# EInkHeader.net
KiCad netlist of a schematic drawn in Altium Designer
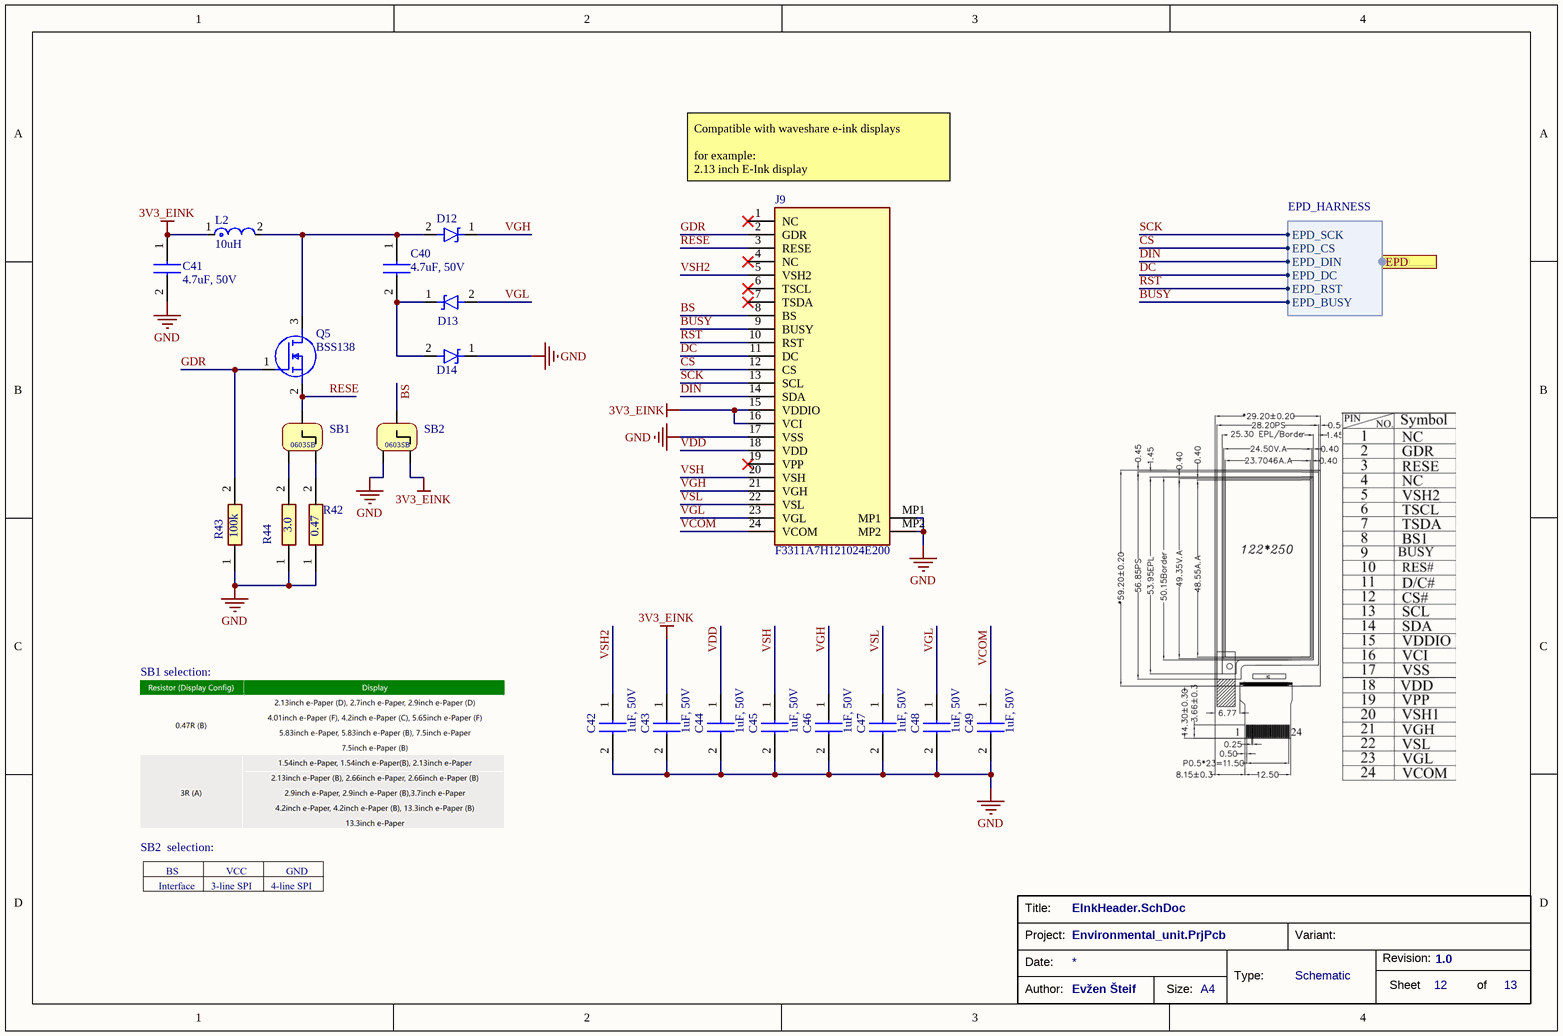
[diagram p0: EInkHeader.SchDoc]

(export (version "E")
  (design (tool "Eeschema 10.0.6"))
  (components
    (comp (ref "C40")
      (value "4.7uF, 50V")
      (footprint "SamacSys:CAPC2012X145N")
      (description "Capacitor")
      (fields
        (field (name "MANUFACTURER_PART_NUMBER") "GRM21BR61H475KE51L")
        (field (name "MOUSER PART NUMBER") "81-GRM21BR61H475KE1L")
      )
      (libsource (lib "*") (part "GRM21BR61H475KE51L"))
    )
    (comp (ref "C41")
      (value "4.7uF, 50V")
      (footprint "SamacSys:CAPC2012X145N")
      (description "Capacitor")
      (fields
        (field (name "MANUFACTURER_PART_NUMBER") "GRM21BR61H475KE51L")
        (field (name "MOUSER PART NUMBER") "81-GRM21BR61H475KE1L")
      )
      (libsource (lib "*") (part "GRM21BR61H475KE51L"))
    )
    (comp (ref "C42")
      (value "1uF, 50V")
      (footprint "SamacSys:CAPC1608X90N")
      (description "Capacitor")
      (fields
        (field (name "MANUFACTURER_PART_NUMBER") "GRT188R61H105KE13D")
        (field (name "MOUSER PART NUMBER") "81-GRT188R61H105KE3D")
      )
      (libsource (lib "*") (part "GRT188R61H105KE13D"))
    )
    (comp (ref "C43")
      (value "1uF, 50V")
      (footprint "SamacSys:CAPC1608X90N")
      (description "Capacitor")
      (fields
        (field (name "MANUFACTURER_PART_NUMBER") "GRT188R61H105KE13D")
        (field (name "MOUSER PART NUMBER") "81-GRT188R61H105KE3D")
      )
      (libsource (lib "*") (part "GRT188R61H105KE13D"))
    )
    (comp (ref "C44")
      (value "1uF, 50V")
      (footprint "SamacSys:CAPC1608X90N")
      (description "Capacitor")
      (fields
        (field (name "MANUFACTURER_PART_NUMBER") "GRT188R61H105KE13D")
        (field (name "MOUSER PART NUMBER") "81-GRT188R61H105KE3D")
      )
      (libsource (lib "*") (part "GRT188R61H105KE13D"))
    )
    (comp (ref "C45")
      (value "1uF, 50V")
      (footprint "SamacSys:CAPC1608X90N")
      (description "Capacitor")
      (fields
        (field (name "MANUFACTURER_PART_NUMBER") "GRT188R61H105KE13D")
        (field (name "MOUSER PART NUMBER") "81-GRT188R61H105KE3D")
      )
      (libsource (lib "*") (part "GRT188R61H105KE13D"))
    )
    (comp (ref "C46")
      (value "1uF, 50V")
      (footprint "SamacSys:CAPC1608X90N")
      (description "Capacitor")
      (fields
        (field (name "MANUFACTURER_PART_NUMBER") "GRT188R61H105KE13D")
        (field (name "MOUSER PART NUMBER") "81-GRT188R61H105KE3D")
      )
      (libsource (lib "*") (part "GRT188R61H105KE13D"))
    )
    (comp (ref "C47")
      (value "1uF, 50V")
      (footprint "SamacSys:CAPC1608X90N")
      (description "Capacitor")
      (fields
        (field (name "MANUFACTURER_PART_NUMBER") "GRT188R61H105KE13D")
        (field (name "MOUSER PART NUMBER") "81-GRT188R61H105KE3D")
      )
      (libsource (lib "*") (part "GRT188R61H105KE13D"))
    )
    (comp (ref "C48")
      (value "1uF, 50V")
      (footprint "SamacSys:CAPC1608X90N")
      (description "Capacitor")
      (fields
        (field (name "MANUFACTURER_PART_NUMBER") "GRT188R61H105KE13D")
        (field (name "MOUSER PART NUMBER") "81-GRT188R61H105KE3D")
      )
      (libsource (lib "*") (part "GRT188R61H105KE13D"))
    )
    (comp (ref "C49")
      (value "1uF, 50V")
      (footprint "SamacSys:CAPC1608X90N")
      (description "Capacitor")
      (fields
        (field (name "MANUFACTURER_PART_NUMBER") "GRT188R61H105KE13D")
        (field (name "MOUSER PART NUMBER") "81-GRT188R61H105KE3D")
      )
      (libsource (lib "*") (part "GRT188R61H105KE13D"))
    )
    (comp (ref "D12")
      (value "MBR0530T1G")
      (footprint "SamacSys:SOD3716X135N")
      (description "Diode")
      (fields (field (name "MOUSER PART NUMBER") "863-MBR0530T1G"))
      (libsource (lib "SamacSys") (part "MBR0530T1G"))
    )
    (comp (ref "D13")
      (value "MBR0530T1G")
      (footprint "SamacSys:SOD3716X135N")
      (description "Diode")
      (fields (field (name "MOUSER PART NUMBER") "863-MBR0530T1G"))
      (libsource (lib "SamacSys") (part "MBR0530T1G"))
    )
    (comp (ref "D14")
      (value "MBR0530T1G")
      (footprint "SamacSys:SOD3716X135N")
      (description "Diode")
      (fields (field (name "MOUSER PART NUMBER") "863-MBR0530T1G"))
      (libsource (lib "SamacSys") (part "MBR0530T1G"))
    )
    (comp (ref "J9")
      (value "F3311A7H121024E200")
      (footprint "SamacSys:F3311A7H121024E200")
      (description "Connector")
      (fields (field (name "MOUSER PART NUMBER") "649-311A7H121024E200"))
      (libsource (lib "SamacSys") (part "F3311A7H121024E200"))
    )
    (comp (ref "L2")
      (value "10uH")
      (footprint "FP-EPL2010_H1_05-MFG")
      (description "EPL2010-103MLC Power inductor, shielded, 20% tol, SMT, RoHS")
      (fields (field (name "TOLERANCE") "20%"))
      (libsource (lib "Altium Content Vault") (part "4cc4b267dca4c8e51f7102f422741d8"))
    )
    (comp (ref "Q5")
      (value "BSS138")
      (footprint "SamacSys:SOT95P240X120-3N")
      (description "MOSFET (N-Channel)")
      (fields (field (name "MOUSER PART NUMBER") "512-BSS138"))
      (libsource (lib "*") (part "BSS138"))
    )
    (comp (ref "R42")
      (value "0.47")
      (footprint "SamacSys:ERJ3_B_BQ_BW_LW_(0603)")
      (description "Resistor")
      (fields
        (field (name "MANUFACTURER_PART_NUMBER") "ERJ-3BQFR47V")
        (field (name "MOUSER PART NUMBER") "667-ERJ-3BQFR47V")
      )
      (libsource (lib "*") (part "ERJ-3BQFR47V"))
    )
    (comp (ref "R43")
      (value "100k")
      (footprint "SamacSys:RESC1005X35N")
      (description "Resistor")
      (fields
        (field (name "MANUFACTURER_PART_NUMBER") "RT0402FRE07100KL")
        (field (name "MOUSER PART NUMBER") "603-RT0402FRE07100KL")
      )
      (libsource (lib "*") (part "RT0402FRE07100KL"))
    )
    (comp (ref "R44")
      (value "3.0")
      (footprint "SamacSys:ERJ3_B_BQ_BW_LW_(0603)")
      (description "Resistor")
      (fields
        (field (name "MANUFACTURER_PART_NUMBER") "ERJ-3RQF3R0V")
        (field (name "MOUSER PART NUMBER") "667-ERJ-3RQF3R0V")
      )
      (libsource (lib "*") (part "ERJ-3RQF3R0V"))
    )
    (comp (ref "SB1")
      (value "SP0603_RIGHT")
      (footprint "SamacSys:SP0603-RIGHT")
      (libsource (lib "SamacSys") (part "SP0603_RIGHT"))
    )
    (comp (ref "SB2")
      (value "SP0603_RIGHT")
      (footprint "SamacSys:SP0603-RIGHT")
      (libsource (lib "SamacSys") (part "SP0603_RIGHT"))
    )
  )
  (nets
    (net (code "2") (name "/BS") (class "Default")
      (node (ref "J9") (pin "8") (pinfunction "BS_8") (pintype "passive"))
      (node (ref "SB2") (pin "1") (pinfunction "1_1") (pintype "passive"))
    )
    (net (code "3") (name "/BUSY") (class "Default")
      (node (ref "J9") (pin "9") (pinfunction "BUSY_9") (pintype "passive"))
    )
    (net (code "4") (name "/CS") (class "Default")
      (node (ref "J9") (pin "12") (pinfunction "CS_12") (pintype "passive"))
    )
    (net (code "5") (name "/DC") (class "Default")
      (node (ref "J9") (pin "11") (pinfunction "DC_11") (pintype "passive"))
    )
    (net (code "6") (name "/DIN") (class "Default")
      (node (ref "J9") (pin "14") (pinfunction "SDA_14") (pintype "passive"))
    )
    (net (code "7") (name "/GDR") (class "Default")
      (node (ref "J9") (pin "2") (pinfunction "GDR_2") (pintype "passive"))
      (node (ref "Q5") (pin "1") (pinfunction "G_1") (pintype "passive"))
      (node (ref "R43") (pin "2") (pinfunction "2_2") (pintype "passive"))
    )
    (net (code "8") (name "/RESE") (class "Default")
      (node (ref "J9") (pin "3") (pinfunction "RESE_3") (pintype "passive"))
      (node (ref "Q5") (pin "2") (pinfunction "S_2") (pintype "passive"))
      (node (ref "SB1") (pin "1") (pinfunction "1_1") (pintype "passive"))
    )
    (net (code "9") (name "/RST") (class "Default")
      (node (ref "J9") (pin "10") (pinfunction "RST_10") (pintype "passive"))
    )
    (net (code "10") (name "/SCK") (class "Default")
      (node (ref "J9") (pin "13") (pinfunction "SCL_13") (pintype "passive"))
    )
    (net (code "11") (name "/VCOM") (class "Default")
      (node (ref "C49") (pin "1") (pinfunction "1_1") (pintype "passive"))
      (node (ref "J9") (pin "24") (pinfunction "VCOM_24") (pintype "passive"))
    )
    (net (code "12") (name "/VDD") (class "Default")
      (node (ref "C44") (pin "1") (pinfunction "1_1") (pintype "passive"))
      (node (ref "J9") (pin "18") (pinfunction "VDD_18") (pintype "passive"))
    )
    (net (code "13") (name "/VGH") (class "Default")
      (node (ref "C46") (pin "1") (pinfunction "1_1") (pintype "passive"))
      (node (ref "D12") (pin "1") (pinfunction "K_1") (pintype "passive"))
      (node (ref "J9") (pin "21") (pinfunction "VGH_21") (pintype "passive"))
    )
    (net (code "14") (name "/VGL") (class "Default")
      (node (ref "C48") (pin "1") (pinfunction "1_1") (pintype "passive"))
      (node (ref "D13") (pin "2") (pinfunction "A_2") (pintype "passive"))
      (node (ref "J9") (pin "23") (pinfunction "VGL_23") (pintype "passive"))
    )
    (net (code "15") (name "/VSH") (class "Default")
      (node (ref "C45") (pin "1") (pinfunction "1_1") (pintype "passive"))
      (node (ref "J9") (pin "20") (pinfunction "VSH_20") (pintype "passive"))
    )
    (net (code "16") (name "/VSH2") (class "Default")
      (node (ref "C42") (pin "1") (pinfunction "1_1") (pintype "passive"))
      (node (ref "J9") (pin "5") (pinfunction "VSH2_5") (pintype "passive"))
    )
    (net (code "17") (name "/VSL") (class "Default")
      (node (ref "C47") (pin "1") (pinfunction "1_1") (pintype "passive"))
      (node (ref "J9") (pin "22") (pinfunction "VSL_22") (pintype "passive"))
    )
    (net (code "19") (name "3V3_EINK") (class "Default")
      (node (ref "C41") (pin "1") (pinfunction "1_1") (pintype "passive"))
      (node (ref "C43") (pin "1") (pinfunction "1_1") (pintype "passive"))
      (node (ref "J9") (pin "15") (pinfunction "VDDIO_15") (pintype "passive"))
      (node (ref "J9") (pin "16") (pinfunction "VCI_16") (pintype "passive"))
      (node (ref "L2") (pin "1") (pinfunction "1_1") (pintype "passive"))
      (node (ref "SB2") (pin "2") (pinfunction "2_2") (pintype "passive"))
    )
    (net (code "20") (name "GND") (class "Default")
      (node (ref "C41") (pin "2") (pinfunction "2_2") (pintype "passive"))
      (node (ref "C42") (pin "2") (pinfunction "2_2") (pintype "passive"))
      (node (ref "C43") (pin "2") (pinfunction "2_2") (pintype "passive"))
      (node (ref "C44") (pin "2") (pinfunction "2_2") (pintype "passive"))
      (node (ref "C45") (pin "2") (pinfunction "2_2") (pintype "passive"))
      (node (ref "C46") (pin "2") (pinfunction "2_2") (pintype "passive"))
      (node (ref "C47") (pin "2") (pinfunction "2_2") (pintype "passive"))
      (node (ref "C48") (pin "2") (pinfunction "2_2") (pintype "passive"))
      (node (ref "C49") (pin "2") (pinfunction "2_2") (pintype "passive"))
      (node (ref "D14") (pin "1") (pinfunction "K_1") (pintype "passive"))
      (node (ref "J9") (pin "17") (pinfunction "VSS_17") (pintype "passive"))
      (node (ref "J9") (pin "MP1") (pinfunction "MP1_MP1") (pintype "passive"))
      (node (ref "J9") (pin "MP2") (pinfunction "MP2_MP2") (pintype "passive"))
      (node (ref "R42") (pin "1") (pinfunction "1_1") (pintype "passive"))
      (node (ref "R43") (pin "1") (pinfunction "1_1") (pintype "passive"))
      (node (ref "R44") (pin "1") (pinfunction "1_1") (pintype "passive"))
      (node (ref "SB2") (pin "3") (pinfunction "3_3") (pintype "passive"))
    )
    (net (code "21") (name "Net-(D12-A)") (class "Default")
      (node (ref "C40") (pin "1") (pinfunction "1_1") (pintype "passive"))
      (node (ref "D12") (pin "2") (pinfunction "A_2") (pintype "passive"))
      (node (ref "L2") (pin "2") (pinfunction "2_2") (pintype "passive"))
      (node (ref "Q5") (pin "3") (pinfunction "D_3") (pintype "passive"))
    )
    (net (code "22") (name "Net-(D13-K)") (class "Default")
      (node (ref "C40") (pin "2") (pinfunction "2_2") (pintype "passive"))
      (node (ref "D13") (pin "1") (pinfunction "K_1") (pintype "passive"))
      (node (ref "D14") (pin "2") (pinfunction "A_2") (pintype "passive"))
    )
    (net (code "23") (name "Net-(R42-Pad2)") (class "Default")
      (node (ref "R42") (pin "2") (pinfunction "2_2") (pintype "passive"))
      (node (ref "SB1") (pin "2") (pinfunction "2_2") (pintype "passive"))
    )
    (net (code "24") (name "Net-(R44-Pad2)") (class "Default")
      (node (ref "R44") (pin "2") (pinfunction "2_2") (pintype "passive"))
      (node (ref "SB1") (pin "3") (pinfunction "3_3") (pintype "passive"))
    )
    (net (code "25") (name "unconnected-(J9-NC-Pad1)") (class "Default")
      (node (ref "J9") (pin "1") (pinfunction "NC_1") (pintype "passive+no_connect"))
    )
    (net (code "26") (name "unconnected-(J9-NC-Pad4)") (class "Default")
      (node (ref "J9") (pin "4") (pinfunction "NC_4") (pintype "passive+no_connect"))
    )
    (net (code "27") (name "unconnected-(J9-TSCL-Pad6)") (class "Default")
      (node (ref "J9") (pin "6") (pinfunction "TSCL_6") (pintype "passive+no_connect"))
    )
    (net (code "28") (name "unconnected-(J9-TSDA-Pad7)") (class "Default")
      (node (ref "J9") (pin "7") (pinfunction "TSDA_7") (pintype "passive+no_connect"))
    )
    (net (code "29") (name "unconnected-(J9-VPP-Pad19)") (class "Default")
      (node (ref "J9") (pin "19") (pinfunction "VPP_19") (pintype "passive+no_connect"))
    )
  )
)
